# Camera.net
KiCad netlist of a schematic drawn in Altium Designer
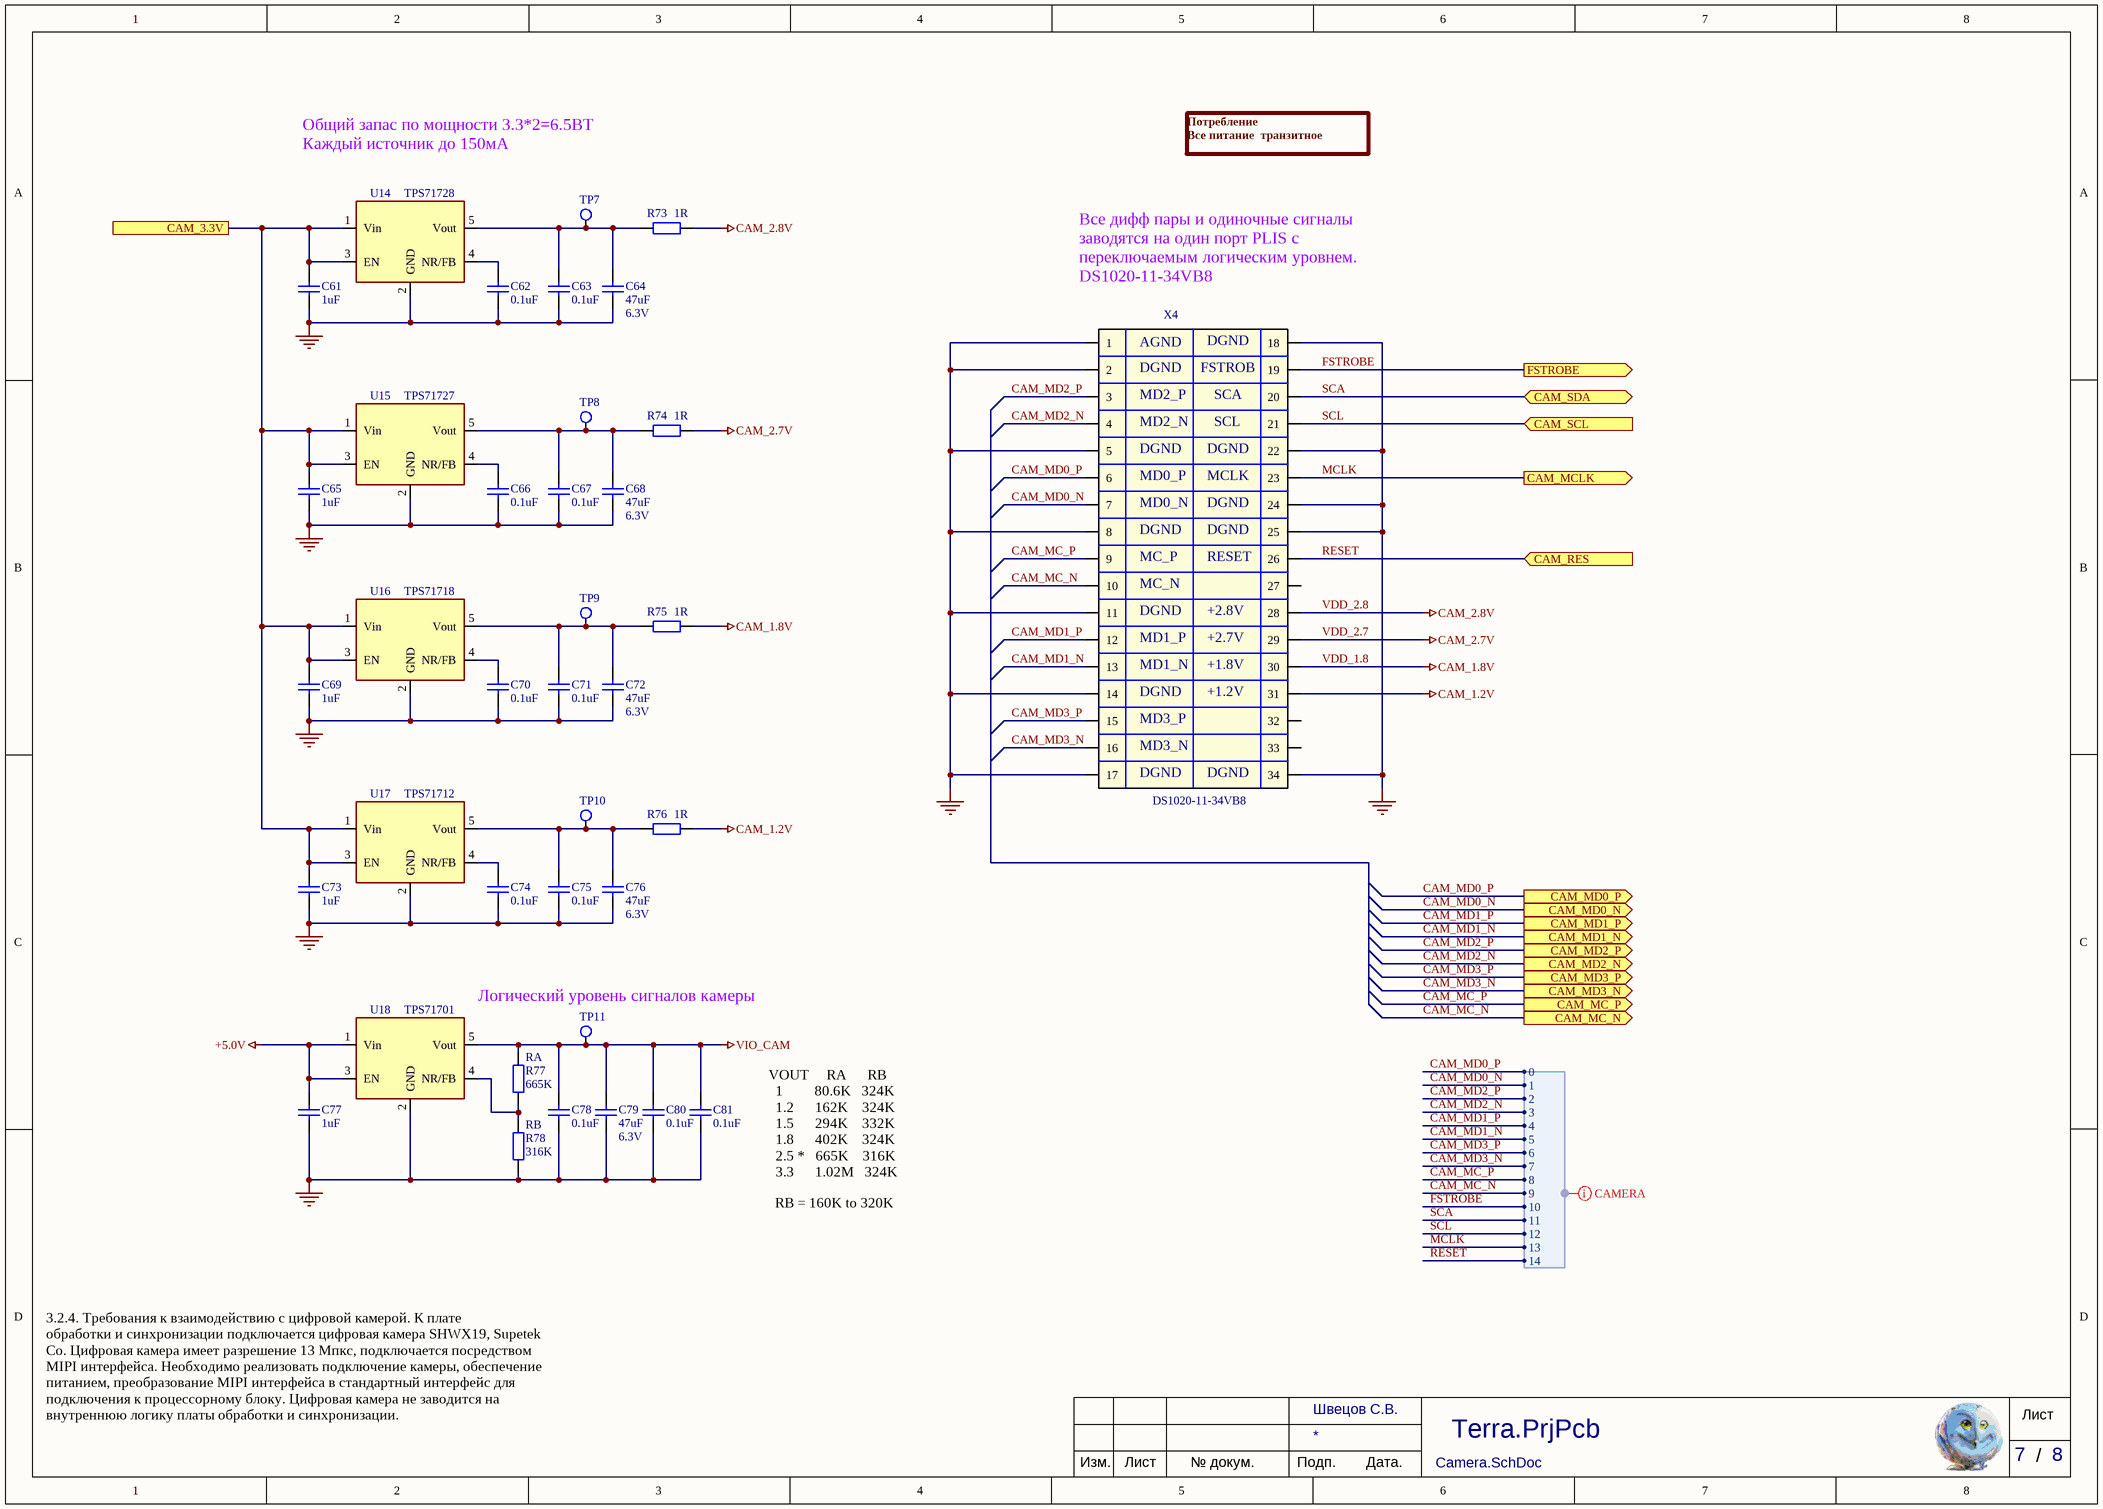
[diagram p0: Camera.SchDoc]

(export (version "E")
  (design (tool "Eeschema 10.0.6"))
  (components
    (comp (ref "C61")
      (value "1uF")
      (footprint "C0603")
      (description "Конденсатор керамический")
      (fields (field (name "Comment") "Cap"))
      (libsource (lib "Terra") (part "Cap"))
    )
    (comp (ref "C62")
      (value "0.1uF")
      (footprint "C0402")
      (description "Конденсатор керамический")
      (fields (field (name "VOLTAGE") "25V") (field (name "Comment") "Cap"))
      (libsource (lib "Terra") (part "Cap"))
    )
    (comp (ref "C63")
      (value "0.1uF")
      (footprint "C0402")
      (description "Конденсатор керамический")
      (fields (field (name "VOLTAGE") "25V") (field (name "Comment") "Cap"))
      (libsource (lib "Terra") (part "Cap"))
    )
    (comp (ref "C64")
      (value "47uF")
      (footprint "C0805")
      (description "C0805C476M9PAC")
      (fields (field (name "VOLTAGE") "6.3V") (field (name "Comment") "Cap"))
      (libsource (lib "Terra") (part "Cap"))
    )
    (comp (ref "C65")
      (value "1uF")
      (footprint "C0603")
      (description "Конденсатор керамический")
      (fields (field (name "Comment") "Cap"))
      (libsource (lib "Terra") (part "Cap"))
    )
    (comp (ref "C66")
      (value "0.1uF")
      (footprint "C0402")
      (description "Конденсатор керамический")
      (fields (field (name "VOLTAGE") "25V") (field (name "Comment") "Cap"))
      (libsource (lib "Terra") (part "Cap"))
    )
    (comp (ref "C67")
      (value "0.1uF")
      (footprint "C0402")
      (description "Конденсатор керамический")
      (fields (field (name "VOLTAGE") "25V") (field (name "Comment") "Cap"))
      (libsource (lib "Terra") (part "Cap"))
    )
    (comp (ref "C68")
      (value "47uF")
      (footprint "C0805")
      (description "C0805C476M9PAC")
      (fields (field (name "VOLTAGE") "6.3V") (field (name "Comment") "Cap"))
      (libsource (lib "Terra") (part "Cap"))
    )
    (comp (ref "C69")
      (value "1uF")
      (footprint "C0603")
      (description "Конденсатор керамический")
      (fields (field (name "Comment") "Cap"))
      (libsource (lib "Terra") (part "Cap"))
    )
    (comp (ref "C70")
      (value "0.1uF")
      (footprint "C0402")
      (description "Конденсатор керамический")
      (fields (field (name "VOLTAGE") "25V") (field (name "Comment") "Cap"))
      (libsource (lib "Terra") (part "Cap"))
    )
    (comp (ref "C71")
      (value "0.1uF")
      (footprint "C0402")
      (description "Конденсатор керамический")
      (fields (field (name "VOLTAGE") "25V") (field (name "Comment") "Cap"))
      (libsource (lib "Terra") (part "Cap"))
    )
    (comp (ref "C72")
      (value "47uF")
      (footprint "C0805")
      (description "C0805C476M9PAC")
      (fields (field (name "VOLTAGE") "6.3V") (field (name "Comment") "Cap"))
      (libsource (lib "Terra") (part "Cap"))
    )
    (comp (ref "C73")
      (value "1uF")
      (footprint "C0603")
      (description "Конденсатор керамический")
      (fields (field (name "Comment") "Cap"))
      (libsource (lib "Terra") (part "Cap"))
    )
    (comp (ref "C74")
      (value "0.1uF")
      (footprint "C0402")
      (description "Конденсатор керамический")
      (fields (field (name "VOLTAGE") "25V") (field (name "Comment") "Cap"))
      (libsource (lib "Terra") (part "Cap"))
    )
    (comp (ref "C75")
      (value "0.1uF")
      (footprint "C0402")
      (description "Конденсатор керамический")
      (fields (field (name "VOLTAGE") "25V") (field (name "Comment") "Cap"))
      (libsource (lib "Terra") (part "Cap"))
    )
    (comp (ref "C76")
      (value "47uF")
      (footprint "C0805")
      (description "C0805C476M9PAC")
      (fields (field (name "VOLTAGE") "6.3V") (field (name "Comment") "Cap"))
      (libsource (lib "Terra") (part "Cap"))
    )
    (comp (ref "C77")
      (value "1uF")
      (footprint "C0603")
      (description "Конденсатор керамический")
      (fields (field (name "Comment") "Cap"))
      (libsource (lib "Terra") (part "Cap"))
    )
    (comp (ref "C78")
      (value "0.1uF")
      (footprint "C0402")
      (description "Конденсатор керамический")
      (fields (field (name "VOLTAGE") "25V") (field (name "Comment") "Cap"))
      (libsource (lib "Terra") (part "Cap"))
    )
    (comp (ref "C79")
      (value "47uF")
      (footprint "C0805")
      (description "C0805C476M9PAC")
      (fields (field (name "VOLTAGE") "6.3V") (field (name "Comment") "Cap"))
      (libsource (lib "Terra") (part "Cap"))
    )
    (comp (ref "C80")
      (value "0.1uF")
      (footprint "C0402")
      (description "Конденсатор керамический")
      (fields (field (name "VOLTAGE") "25V") (field (name "Comment") "Cap"))
      (libsource (lib "Terra") (part "Cap"))
    )
    (comp (ref "C81")
      (value "0.1uF")
      (footprint "C0402")
      (description "Конденсатор керамический")
      (fields (field (name "VOLTAGE") "25V") (field (name "Comment") "Cap"))
      (libsource (lib "Terra") (part "Cap"))
    )
    (comp (ref "R73")
      (value "1R")
      (footprint "R0402")
      (description "Резистор")
      (fields (field (name "Comment") "Res2"))
      (libsource (lib "") (part "Res2_1"))
    )
    (comp (ref "R74")
      (value "1R")
      (footprint "R0402")
      (description "Резистор")
      (fields (field (name "Comment") "Res2"))
      (libsource (lib "") (part "Res2_1"))
    )
    (comp (ref "R75")
      (value "1R")
      (footprint "R0402")
      (description "Резистор")
      (fields (field (name "Comment") "Res2"))
      (libsource (lib "") (part "Res2_1"))
    )
    (comp (ref "R76")
      (value "1R")
      (footprint "R0402")
      (description "Резистор")
      (fields (field (name "Comment") "Res2"))
      (libsource (lib "") (part "Res2_1"))
    )
    (comp (ref "R77")
      (value "665K")
      (footprint "R0402")
      (description "Резистор")
      (fields (field (name "PARAMETER 1") "RA") (field (name "Comment") "Res2"))
      (libsource (lib "Terra") (part "Res2"))
    )
    (comp (ref "R78")
      (value "316K")
      (footprint "R0402")
      (description "Резистор")
      (fields (field (name "PARAMETER 1") "RB") (field (name "Comment") "Res2"))
      (libsource (lib "Terra") (part "Res2"))
    )
    (comp (ref "TP7")
      (value "~")
      (footprint "TP_0MM5_1MM0")
      (description "Тестовая точка на плате")
      (libsource (lib "*") (part "Test_Point"))
    )
    (comp (ref "TP8")
      (value "~")
      (footprint "TP_0MM5_1MM0")
      (description "Тестовая точка на плате")
      (libsource (lib "*") (part "Test_Point"))
    )
    (comp (ref "TP9")
      (value "~")
      (footprint "TP_0MM5_1MM0")
      (description "Тестовая точка на плате")
      (libsource (lib "*") (part "Test_Point"))
    )
    (comp (ref "TP10")
      (value "~")
      (footprint "TP_0MM5_1MM0")
      (description "Тестовая точка на плате")
      (libsource (lib "*") (part "Test_Point"))
    )
    (comp (ref "TP11")
      (value "~")
      (footprint "TP_0MM5_1MM0")
      (description "Тестовая точка на плате")
      (libsource (lib "*") (part "Test_Point"))
    )
    (comp (ref "U14")
      (value "TPS71728")
      (footprint "SOT23_5")
      (description "Линейный стабилизатор +2.8В")
      (libsource (lib "AVRlinux") (part "TPS71718"))
    )
    (comp (ref "U15")
      (value "TPS71727")
      (footprint "SOT23_5")
      (description "Линейный стабилизатор +2.7В")
      (libsource (lib "AVRlinux") (part "TPS71718"))
    )
    (comp (ref "U16")
      (value "TPS71718")
      (footprint "SOT23_5")
      (description "Линейный стабилизатор +1.8В")
      (libsource (lib "AVRlinux") (part "TPS71718"))
    )
    (comp (ref "U17")
      (value "TPS71712")
      (footprint "SOT23_5")
      (description "Линейный стабилизатор +1.2В")
      (libsource (lib "AVRlinux") (part "TPS71718"))
    )
    (comp (ref "U18")
      (value "TPS71701")
      (footprint "SOT23_5")
      (description "Линейный стабилизатор +1.2В")
      (libsource (lib "AVRlinux") (part "TPS71718"))
    )
    (comp (ref "X4")
      (value "DS1020-11-34VB8")
      (footprint "DS1020-11-34VB8")
      (description "Розетка  Kyocera")
      (libsource (lib "*") (part "CON2x17_1"))
    )
  )
  (nets
    (net (code "1") (name "+5.0V") (class "Default")
      (node (ref "C77") (pin "1") (pinfunction "1_1") (pintype "passive"))
      (node (ref "U18") (pin "1") (pinfunction "Vin_1") (pintype "passive"))
      (node (ref "U18") (pin "3") (pinfunction "EN_3") (pintype "passive"))
    )
    (net (code "2") (name "/CAM_3.3V") (class "Default")
      (node (ref "C61") (pin "1") (pinfunction "1_1") (pintype "passive"))
      (node (ref "C65") (pin "1") (pinfunction "1_1") (pintype "passive"))
      (node (ref "C69") (pin "1") (pinfunction "1_1") (pintype "passive"))
      (node (ref "C73") (pin "1") (pinfunction "1_1") (pintype "passive"))
      (node (ref "U14") (pin "1") (pinfunction "Vin_1") (pintype "passive"))
      (node (ref "U14") (pin "3") (pinfunction "EN_3") (pintype "passive"))
      (node (ref "U15") (pin "1") (pinfunction "Vin_1") (pintype "passive"))
      (node (ref "U15") (pin "3") (pinfunction "EN_3") (pintype "passive"))
      (node (ref "U16") (pin "1") (pinfunction "Vin_1") (pintype "passive"))
      (node (ref "U16") (pin "3") (pinfunction "EN_3") (pintype "passive"))
      (node (ref "U17") (pin "1") (pinfunction "Vin_1") (pintype "passive"))
      (node (ref "U17") (pin "3") (pinfunction "EN_3") (pintype "passive"))
    )
    (net (code "3") (name "/CAM_MC_N") (class "Default")
      (node (ref "X4") (pin "10") (pinfunction "10_10") (pintype "passive"))
    )
    (net (code "4") (name "/CAM_MC_P") (class "Default")
      (node (ref "X4") (pin "9") (pinfunction "9_9") (pintype "passive"))
    )
    (net (code "5") (name "/CAM_MD0_N") (class "Default")
      (node (ref "X4") (pin "7") (pinfunction "7_7") (pintype "passive"))
    )
    (net (code "6") (name "/CAM_MD0_P") (class "Default")
      (node (ref "X4") (pin "6") (pinfunction "6_6") (pintype "passive"))
    )
    (net (code "7") (name "/CAM_MD1_N") (class "Default")
      (node (ref "X4") (pin "13") (pinfunction "13_13") (pintype "passive"))
    )
    (net (code "8") (name "/CAM_MD1_P") (class "Default")
      (node (ref "X4") (pin "12") (pinfunction "12_12") (pintype "passive"))
    )
    (net (code "9") (name "/CAM_MD2_N") (class "Default")
      (node (ref "X4") (pin "4") (pinfunction "4_4") (pintype "passive"))
    )
    (net (code "10") (name "/CAM_MD2_P") (class "Default")
      (node (ref "X4") (pin "3") (pinfunction "3_3") (pintype "passive"))
    )
    (net (code "11") (name "/CAM_MD3_N") (class "Default")
      (node (ref "X4") (pin "16") (pinfunction "16_16") (pintype "passive"))
    )
    (net (code "12") (name "/CAM_MD3_P") (class "Default")
      (node (ref "X4") (pin "15") (pinfunction "15_15") (pintype "passive"))
    )
    (net (code "13") (name "/FSTROBE") (class "Default")
      (node (ref "X4") (pin "19") (pinfunction "19_19") (pintype "passive"))
    )
    (net (code "14") (name "/MCLK") (class "Default")
      (node (ref "X4") (pin "23") (pinfunction "23_23") (pintype "passive"))
    )
    (net (code "15") (name "/RESET") (class "Default")
      (node (ref "X4") (pin "26") (pinfunction "26_26") (pintype "passive"))
    )
    (net (code "16") (name "/SCA") (class "Default")
      (node (ref "X4") (pin "20") (pinfunction "20_20") (pintype "passive"))
    )
    (net (code "17") (name "/SCL") (class "Default")
      (node (ref "X4") (pin "21") (pinfunction "21_21") (pintype "passive"))
    )
    (net (code "18") (name "CAM_1.2V") (class "Default")
      (node (ref "R76") (pin "1") (pinfunction "1_1") (pintype "passive"))
      (node (ref "X4") (pin "31") (pinfunction "31_31") (pintype "passive"))
    )
    (net (code "19") (name "CAM_1.8V") (class "Default")
      (node (ref "R75") (pin "1") (pinfunction "1_1") (pintype "passive"))
      (node (ref "X4") (pin "30") (pinfunction "30_30") (pintype "passive"))
    )
    (net (code "20") (name "CAM_2.7V") (class "Default")
      (node (ref "R74") (pin "1") (pinfunction "1_1") (pintype "passive"))
      (node (ref "X4") (pin "29") (pinfunction "29_29") (pintype "passive"))
    )
    (net (code "21") (name "CAM_2.8V") (class "Default")
      (node (ref "R73") (pin "1") (pinfunction "1_1") (pintype "passive"))
      (node (ref "X4") (pin "28") (pinfunction "28_28") (pintype "passive"))
    )
    (net (code "22") (name "GND") (class "Default")
      (node (ref "C61") (pin "2") (pinfunction "2_2") (pintype "passive"))
      (node (ref "C62") (pin "2") (pinfunction "2_2") (pintype "passive"))
      (node (ref "C63") (pin "2") (pinfunction "2_2") (pintype "passive"))
      (node (ref "C64") (pin "2") (pinfunction "2_2") (pintype "passive"))
      (node (ref "C65") (pin "2") (pinfunction "2_2") (pintype "passive"))
      (node (ref "C66") (pin "2") (pinfunction "2_2") (pintype "passive"))
      (node (ref "C67") (pin "2") (pinfunction "2_2") (pintype "passive"))
      (node (ref "C68") (pin "2") (pinfunction "2_2") (pintype "passive"))
      (node (ref "C69") (pin "2") (pinfunction "2_2") (pintype "passive"))
      (node (ref "C70") (pin "2") (pinfunction "2_2") (pintype "passive"))
      (node (ref "C71") (pin "2") (pinfunction "2_2") (pintype "passive"))
      (node (ref "C72") (pin "2") (pinfunction "2_2") (pintype "passive"))
      (node (ref "C73") (pin "2") (pinfunction "2_2") (pintype "passive"))
      (node (ref "C74") (pin "2") (pinfunction "2_2") (pintype "passive"))
      (node (ref "C75") (pin "2") (pinfunction "2_2") (pintype "passive"))
      (node (ref "C76") (pin "2") (pinfunction "2_2") (pintype "passive"))
      (node (ref "C77") (pin "2") (pinfunction "2_2") (pintype "passive"))
      (node (ref "C78") (pin "2") (pinfunction "2_2") (pintype "passive"))
      (node (ref "C79") (pin "2") (pinfunction "2_2") (pintype "passive"))
      (node (ref "C80") (pin "2") (pinfunction "2_2") (pintype "passive"))
      (node (ref "C81") (pin "2") (pinfunction "2_2") (pintype "passive"))
      (node (ref "R78") (pin "2") (pinfunction "2_2") (pintype "passive"))
      (node (ref "U14") (pin "2") (pinfunction "GND_2") (pintype "passive"))
      (node (ref "U15") (pin "2") (pinfunction "GND_2") (pintype "passive"))
      (node (ref "U16") (pin "2") (pinfunction "GND_2") (pintype "passive"))
      (node (ref "U17") (pin "2") (pinfunction "GND_2") (pintype "passive"))
      (node (ref "U18") (pin "2") (pinfunction "GND_2") (pintype "passive"))
      (node (ref "X4") (pin "1") (pinfunction "1_1") (pintype "passive"))
      (node (ref "X4") (pin "11") (pinfunction "11_11") (pintype "passive"))
      (node (ref "X4") (pin "14") (pinfunction "14_14") (pintype "passive"))
      (node (ref "X4") (pin "17") (pinfunction "17_17") (pintype "passive"))
      (node (ref "X4") (pin "18") (pinfunction "18_18") (pintype "passive"))
      (node (ref "X4") (pin "2") (pinfunction "2_2") (pintype "passive"))
      (node (ref "X4") (pin "22") (pinfunction "22_22") (pintype "passive"))
      (node (ref "X4") (pin "24") (pinfunction "24_24") (pintype "passive"))
      (node (ref "X4") (pin "25") (pinfunction "25_25") (pintype "passive"))
      (node (ref "X4") (pin "34") (pinfunction "34_34") (pintype "passive"))
      (node (ref "X4") (pin "5") (pinfunction "5_5") (pintype "passive"))
      (node (ref "X4") (pin "8") (pinfunction "8_8") (pintype "passive"))
    )
    (net (code "23") (name "Net-(TP7-e1)") (class "Default")
      (node (ref "C63") (pin "1") (pinfunction "1_1") (pintype "passive"))
      (node (ref "C64") (pin "1") (pinfunction "1_1") (pintype "passive"))
      (node (ref "R73") (pin "2") (pinfunction "2_2") (pintype "passive"))
      (node (ref "TP7") (pin "1") (pinfunction "e1_1") (pintype "passive"))
      (node (ref "U14") (pin "5") (pinfunction "Vout_5") (pintype "passive"))
    )
    (net (code "24") (name "Net-(TP8-e1)") (class "Default")
      (node (ref "C67") (pin "1") (pinfunction "1_1") (pintype "passive"))
      (node (ref "C68") (pin "1") (pinfunction "1_1") (pintype "passive"))
      (node (ref "R74") (pin "2") (pinfunction "2_2") (pintype "passive"))
      (node (ref "TP8") (pin "1") (pinfunction "e1_1") (pintype "passive"))
      (node (ref "U15") (pin "5") (pinfunction "Vout_5") (pintype "passive"))
    )
    (net (code "25") (name "Net-(TP9-e1)") (class "Default")
      (node (ref "C71") (pin "1") (pinfunction "1_1") (pintype "passive"))
      (node (ref "C72") (pin "1") (pinfunction "1_1") (pintype "passive"))
      (node (ref "R75") (pin "2") (pinfunction "2_2") (pintype "passive"))
      (node (ref "TP9") (pin "1") (pinfunction "e1_1") (pintype "passive"))
      (node (ref "U16") (pin "5") (pinfunction "Vout_5") (pintype "passive"))
    )
    (net (code "26") (name "Net-(TP10-e1)") (class "Default")
      (node (ref "C75") (pin "1") (pinfunction "1_1") (pintype "passive"))
      (node (ref "C76") (pin "1") (pinfunction "1_1") (pintype "passive"))
      (node (ref "R76") (pin "2") (pinfunction "2_2") (pintype "passive"))
      (node (ref "TP10") (pin "1") (pinfunction "e1_1") (pintype "passive"))
      (node (ref "U17") (pin "5") (pinfunction "Vout_5") (pintype "passive"))
    )
    (net (code "27") (name "Net-(U14-NR{slash}FB)") (class "Default")
      (node (ref "C62") (pin "1") (pinfunction "1_1") (pintype "passive"))
      (node (ref "U14") (pin "4") (pinfunction "NR/FB_4") (pintype "passive"))
    )
    (net (code "28") (name "Net-(U15-NR{slash}FB)") (class "Default")
      (node (ref "C66") (pin "1") (pinfunction "1_1") (pintype "passive"))
      (node (ref "U15") (pin "4") (pinfunction "NR/FB_4") (pintype "passive"))
    )
    (net (code "29") (name "Net-(U16-NR{slash}FB)") (class "Default")
      (node (ref "C70") (pin "1") (pinfunction "1_1") (pintype "passive"))
      (node (ref "U16") (pin "4") (pinfunction "NR/FB_4") (pintype "passive"))
    )
    (net (code "30") (name "Net-(U17-NR{slash}FB)") (class "Default")
      (node (ref "C74") (pin "1") (pinfunction "1_1") (pintype "passive"))
      (node (ref "U17") (pin "4") (pinfunction "NR/FB_4") (pintype "passive"))
    )
    (net (code "31") (name "Net-(U18-NR{slash}FB)") (class "Default")
      (node (ref "R77") (pin "2") (pinfunction "2_2") (pintype "passive"))
      (node (ref "R78") (pin "1") (pinfunction "1_1") (pintype "passive"))
      (node (ref "U18") (pin "4") (pinfunction "NR/FB_4") (pintype "passive"))
    )
    (net (code "32") (name "VIO_CAM") (class "Default")
      (node (ref "C78") (pin "1") (pinfunction "1_1") (pintype "passive"))
      (node (ref "C79") (pin "1") (pinfunction "1_1") (pintype "passive"))
      (node (ref "C80") (pin "1") (pinfunction "1_1") (pintype "passive"))
      (node (ref "C81") (pin "1") (pinfunction "1_1") (pintype "passive"))
      (node (ref "R77") (pin "1") (pinfunction "1_1") (pintype "passive"))
      (node (ref "TP11") (pin "1") (pinfunction "e1_1") (pintype "passive"))
      (node (ref "U18") (pin "5") (pinfunction "Vout_5") (pintype "passive"))
    )
    (net (code "33") (name "unconnected-(X4-Pad27)") (class "Default")
      (node (ref "X4") (pin "27") (pinfunction "27_27") (pintype "passive"))
    )
    (net (code "34") (name "unconnected-(X4-Pad32)") (class "Default")
      (node (ref "X4") (pin "32") (pinfunction "32_32") (pintype "passive"))
    )
    (net (code "35") (name "unconnected-(X4-Pad33)") (class "Default")
      (node (ref "X4") (pin "33") (pinfunction "33_33") (pintype "passive"))
    )
  )
)
